# bga_test.net
KiCad netlist of a schematic drawn in EAGLE
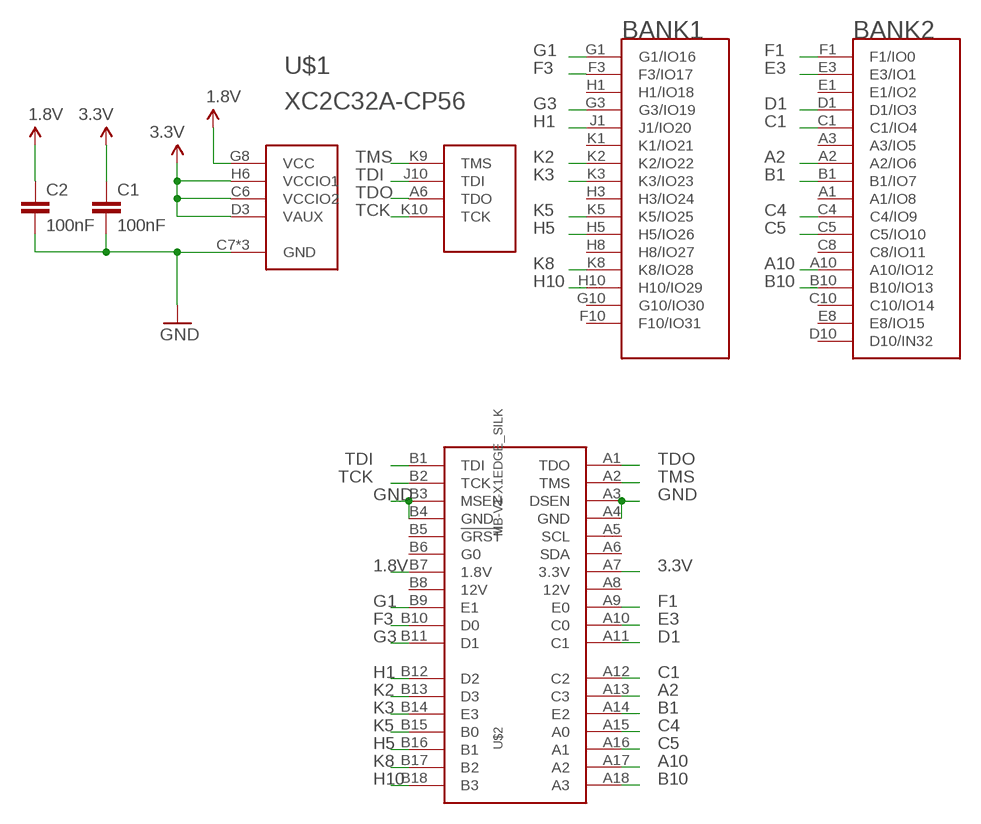
[diagram p0: schematic, sheet 1]

(export (version "E")
  (design (tool "Eeschema 10.0.6"))
  (components
    (comp (ref "C1")
      (value "100nF")
      (footprint "eagle-import:0402-CAP")
      (libsource (lib "eagle-import") (part "CAP0402-CAP"))
    )
    (comp (ref "C2")
      (value "100nF")
      (footprint "eagle-import:0402-CAP")
      (libsource (lib "eagle-import") (part "CAP0402-CAP"))
    )
    (comp (ref "U$1")
      (value "XC2C32A-CP56")
      (footprint "eagle-import:XILINX_CP56")
      (libsource (lib "eagle-import") (part "XC2C32A-CP56"))
    )
    (comp (ref "U$2")
      (value "MB-V1-X1EDGE_SILK")
      (footprint "eagle-import:MB-V1-X1-EDGE")
      (libsource (lib "eagle-import") (part "MB-V1-X1EDGE_SILK"))
    )
  )
  (nets
    (net (code "1") (name "/A2") (class "Default")
      (node (ref "U$1") (pin "A2") (pinfunction "A2/IO6_A2") (pintype "bidirectional"))
      (node (ref "U$2") (pin "A13") (pinfunction "C3_A13") (pintype "bidirectional"))
    )
    (net (code "2") (name "/A10") (class "Default")
      (node (ref "U$1") (pin "A10") (pinfunction "A10/IO12_A10") (pintype "bidirectional"))
      (node (ref "U$2") (pin "A17") (pinfunction "A2_A17") (pintype "bidirectional"))
    )
    (net (code "3") (name "/B1") (class "Default")
      (node (ref "U$1") (pin "B1") (pinfunction "B1/IO7_B1") (pintype "bidirectional"))
      (node (ref "U$2") (pin "A14") (pinfunction "E2_A14") (pintype "bidirectional"))
    )
    (net (code "4") (name "/B10") (class "Default")
      (node (ref "U$1") (pin "B10") (pinfunction "B10/IO13_B10") (pintype "bidirectional"))
      (node (ref "U$2") (pin "A18") (pinfunction "A3_A18") (pintype "bidirectional"))
    )
    (net (code "5") (name "/C1") (class "Default")
      (node (ref "U$1") (pin "C1") (pinfunction "C1/IO4_C1") (pintype "bidirectional"))
      (node (ref "U$2") (pin "A12") (pinfunction "C2_A12") (pintype "bidirectional"))
    )
    (net (code "6") (name "/C4") (class "Default")
      (node (ref "U$1") (pin "C4") (pinfunction "C4/IO9_C4") (pintype "bidirectional"))
      (node (ref "U$2") (pin "A15") (pinfunction "A0_A15") (pintype "bidirectional"))
    )
    (net (code "7") (name "/C5") (class "Default")
      (node (ref "U$1") (pin "C5") (pinfunction "C5/IO10_C5") (pintype "bidirectional"))
      (node (ref "U$2") (pin "A16") (pinfunction "A1_A16") (pintype "bidirectional"))
    )
    (net (code "8") (name "/D1") (class "Default")
      (node (ref "U$1") (pin "D1") (pinfunction "D1/IO3_D1") (pintype "bidirectional"))
      (node (ref "U$2") (pin "A11") (pinfunction "C1_A11") (pintype "bidirectional"))
    )
    (net (code "9") (name "/E3") (class "Default")
      (node (ref "U$1") (pin "E3") (pinfunction "E3/IO1_E3") (pintype "bidirectional"))
      (node (ref "U$2") (pin "A10") (pinfunction "C0_A10") (pintype "bidirectional"))
    )
    (net (code "10") (name "/F1") (class "Default")
      (node (ref "U$1") (pin "F1") (pinfunction "F1/IO0_F1") (pintype "bidirectional"))
      (node (ref "U$2") (pin "A9") (pinfunction "E0_A9") (pintype "bidirectional"))
    )
    (net (code "11") (name "/F3") (class "Default")
      (node (ref "U$1") (pin "F3") (pinfunction "F3/IO17_F3") (pintype "bidirectional"))
      (node (ref "U$2") (pin "B10") (pinfunction "D0_B10") (pintype "bidirectional"))
    )
    (net (code "12") (name "/G1") (class "Default")
      (node (ref "U$1") (pin "G1") (pinfunction "G1/IO16_G1") (pintype "bidirectional"))
      (node (ref "U$2") (pin "B9") (pinfunction "E1_B9") (pintype "bidirectional"))
    )
    (net (code "13") (name "/G3") (class "Default")
      (node (ref "U$1") (pin "G3") (pinfunction "G3/IO19_G3") (pintype "bidirectional"))
      (node (ref "U$2") (pin "B11") (pinfunction "D1_B11") (pintype "bidirectional"))
    )
    (net (code "14") (name "/H1") (class "Default")
      (node (ref "U$1") (pin "J1") (pinfunction "J1/IO20_J1") (pintype "bidirectional"))
      (node (ref "U$2") (pin "B12") (pinfunction "D2_B12") (pintype "bidirectional"))
    )
    (net (code "15") (name "/H5") (class "Default")
      (node (ref "U$1") (pin "H5") (pinfunction "H5/IO26_H5") (pintype "bidirectional"))
      (node (ref "U$2") (pin "B16") (pinfunction "B1_B16") (pintype "bidirectional"))
    )
    (net (code "16") (name "/H10") (class "Default")
      (node (ref "U$1") (pin "H10") (pinfunction "H10/IO29_H10") (pintype "bidirectional"))
      (node (ref "U$2") (pin "B18") (pinfunction "B3_B18") (pintype "bidirectional"))
    )
    (net (code "17") (name "/K2") (class "Default")
      (node (ref "U$1") (pin "K2") (pinfunction "K2/IO22_K2") (pintype "bidirectional"))
      (node (ref "U$2") (pin "B13") (pinfunction "D3_B13") (pintype "bidirectional"))
    )
    (net (code "18") (name "/K3") (class "Default")
      (node (ref "U$1") (pin "K3") (pinfunction "K3/IO23_K3") (pintype "bidirectional"))
      (node (ref "U$2") (pin "B14") (pinfunction "E3_B14") (pintype "bidirectional"))
    )
    (net (code "19") (name "/K5") (class "Default")
      (node (ref "U$1") (pin "K5") (pinfunction "K5/IO25_K5") (pintype "bidirectional"))
      (node (ref "U$2") (pin "B15") (pinfunction "B0_B15") (pintype "bidirectional"))
    )
    (net (code "20") (name "/K8") (class "Default")
      (node (ref "U$1") (pin "K8") (pinfunction "K8/IO28_K8") (pintype "bidirectional"))
      (node (ref "U$2") (pin "B17") (pinfunction "B2_B17") (pintype "bidirectional"))
    )
    (net (code "21") (name "/TCK") (class "Default")
      (node (ref "U$1") (pin "K10") (pinfunction "TCK_K10") (pintype "bidirectional"))
      (node (ref "U$2") (pin "B2") (pinfunction "TCK_B2") (pintype "bidirectional"))
    )
    (net (code "22") (name "/TDI") (class "Default")
      (node (ref "U$1") (pin "J10") (pinfunction "TDI_J10") (pintype "bidirectional"))
      (node (ref "U$2") (pin "B1") (pinfunction "TDI_B1") (pintype "bidirectional"))
    )
    (net (code "23") (name "/TDO") (class "Default")
      (node (ref "U$1") (pin "A6") (pinfunction "TDO_A6") (pintype "bidirectional"))
      (node (ref "U$2") (pin "A1") (pinfunction "TDO_A1") (pintype "bidirectional"))
    )
    (net (code "24") (name "/TMS") (class "Default")
      (node (ref "U$1") (pin "K9") (pinfunction "TMS_K9") (pintype "bidirectional"))
      (node (ref "U$2") (pin "A2") (pinfunction "TMS_A2") (pintype "bidirectional"))
    )
    (net (code "25") (name "1.8V") (class "Default")
      (node (ref "C2") (pin "1") (pinfunction "1_1") (pintype "passive"))
      (node (ref "U$1") (pin "G8") (pinfunction "VCC_G8") (pintype "bidirectional"))
      (node (ref "U$2") (pin "B7") (pinfunction "1.8V_B7") (pintype "bidirectional"))
    )
    (net (code "26") (name "3.3V") (class "Default")
      (node (ref "C1") (pin "1") (pinfunction "1_1") (pintype "passive"))
      (node (ref "U$1") (pin "C6") (pinfunction "VCCIO2_C6") (pintype "bidirectional"))
      (node (ref "U$1") (pin "D3") (pinfunction "VAUX_D3") (pintype "bidirectional"))
      (node (ref "U$1") (pin "H6") (pinfunction "VCCIO1_H6") (pintype "bidirectional"))
      (node (ref "U$2") (pin "A7") (pinfunction "3.3V_A7") (pintype "bidirectional"))
    )
    (net (code "27") (name "GND") (class "Default")
      (node (ref "C1") (pin "2") (pinfunction "2_2") (pintype "passive"))
      (node (ref "C2") (pin "2") (pinfunction "2_2") (pintype "passive"))
      (node (ref "U$1") (pin "C7") (pinfunction "GND_C7") (pintype "bidirectional"))
      (node (ref "U$1") (pin "F8") (pinfunction "GND_F8") (pintype "bidirectional"))
      (node (ref "U$1") (pin "H4") (pinfunction "GND_H4") (pintype "bidirectional"))
      (node (ref "U$2") (pin "A3") (pinfunction "DSEN_A3") (pintype "bidirectional"))
      (node (ref "U$2") (pin "A4") (pinfunction "GND_A4") (pintype "bidirectional"))
      (node (ref "U$2") (pin "B3") (pinfunction "MSEN_B3") (pintype "bidirectional"))
      (node (ref "U$2") (pin "B4") (pinfunction "GND_B4") (pintype "bidirectional"))
    )
    (net (code "28") (name "unconnected-(U$1A-A1{slash}IO8-PadA1)") (class "Default")
      (node (ref "U$1") (pin "A1") (pinfunction "A1/IO8_A1") (pintype "bidirectional"))
    )
    (net (code "29") (name "unconnected-(U$1A-A3{slash}IO5-PadA3)") (class "Default")
      (node (ref "U$1") (pin "A3") (pinfunction "A3/IO5_A3") (pintype "bidirectional"))
    )
    (net (code "30") (name "unconnected-(U$1A-C8{slash}IO11-PadC8)") (class "Default")
      (node (ref "U$1") (pin "C8") (pinfunction "C8/IO11_C8") (pintype "bidirectional"))
    )
    (net (code "31") (name "unconnected-(U$1A-C10{slash}IO14-PadC10)") (class "Default")
      (node (ref "U$1") (pin "C10") (pinfunction "C10/IO14_C10") (pintype "bidirectional"))
    )
    (net (code "32") (name "unconnected-(U$1A-D10{slash}IN32-PadD10)") (class "Default")
      (node (ref "U$1") (pin "D10") (pinfunction "D10/IN32_D10") (pintype "bidirectional"))
    )
    (net (code "33") (name "unconnected-(U$1A-E1{slash}IO2-PadE1)") (class "Default")
      (node (ref "U$1") (pin "E1") (pinfunction "E1/IO2_E1") (pintype "bidirectional"))
    )
    (net (code "34") (name "unconnected-(U$1A-E8{slash}IO15-PadE8)") (class "Default")
      (node (ref "U$1") (pin "E8") (pinfunction "E8/IO15_E8") (pintype "bidirectional"))
    )
    (net (code "35") (name "unconnected-(U$1A-F10{slash}IO31-PadF10)") (class "Default")
      (node (ref "U$1") (pin "F10") (pinfunction "F10/IO31_F10") (pintype "bidirectional"))
    )
    (net (code "36") (name "unconnected-(U$1A-G10{slash}IO30-PadG10)") (class "Default")
      (node (ref "U$1") (pin "G10") (pinfunction "G10/IO30_G10") (pintype "bidirectional"))
    )
    (net (code "37") (name "unconnected-(U$1A-H1{slash}IO18-PadH1)") (class "Default")
      (node (ref "U$1") (pin "H1") (pinfunction "H1/IO18_H1") (pintype "bidirectional"))
    )
    (net (code "38") (name "unconnected-(U$1A-H3{slash}IO24-PadH3)") (class "Default")
      (node (ref "U$1") (pin "H3") (pinfunction "H3/IO24_H3") (pintype "bidirectional"))
    )
    (net (code "39") (name "unconnected-(U$1A-H8{slash}IO27-PadH8)") (class "Default")
      (node (ref "U$1") (pin "H8") (pinfunction "H8/IO27_H8") (pintype "bidirectional"))
    )
    (net (code "40") (name "unconnected-(U$1A-K1{slash}IO21-PadK1)") (class "Default")
      (node (ref "U$1") (pin "K1") (pinfunction "K1/IO21_K1") (pintype "bidirectional"))
    )
    (net (code "41") (name "unconnected-(U$2-12V-PadA8)") (class "Default")
      (node (ref "U$2") (pin "A8") (pinfunction "12V_A8") (pintype "bidirectional"))
    )
    (net (code "42") (name "unconnected-(U$2-12V-PadB8)") (class "Default")
      (node (ref "U$2") (pin "B8") (pinfunction "12V_B8") (pintype "bidirectional"))
    )
    (net (code "43") (name "unconnected-(U$2-G0-PadB6)") (class "Default")
      (node (ref "U$2") (pin "B6") (pinfunction "G0_B6") (pintype "bidirectional"))
    )
    (net (code "44") (name "unconnected-(U$2-SCL-PadA5)") (class "Default")
      (node (ref "U$2") (pin "A5") (pinfunction "SCL_A5") (pintype "bidirectional"))
    )
    (net (code "45") (name "unconnected-(U$2-SDA-PadA6)") (class "Default")
      (node (ref "U$2") (pin "A6") (pinfunction "SDA_A6") (pintype "bidirectional"))
    )
    (net (code "46") (name "unconnected-(U$2-~{GRST}-PadB5)") (class "Default")
      (node (ref "U$2") (pin "B5") (pinfunction "~{GRST}_B5") (pintype "bidirectional"))
    )
  )
)
